# External_Sensor_Schematic.net
KiCad netlist of a schematic drawn in EAGLE
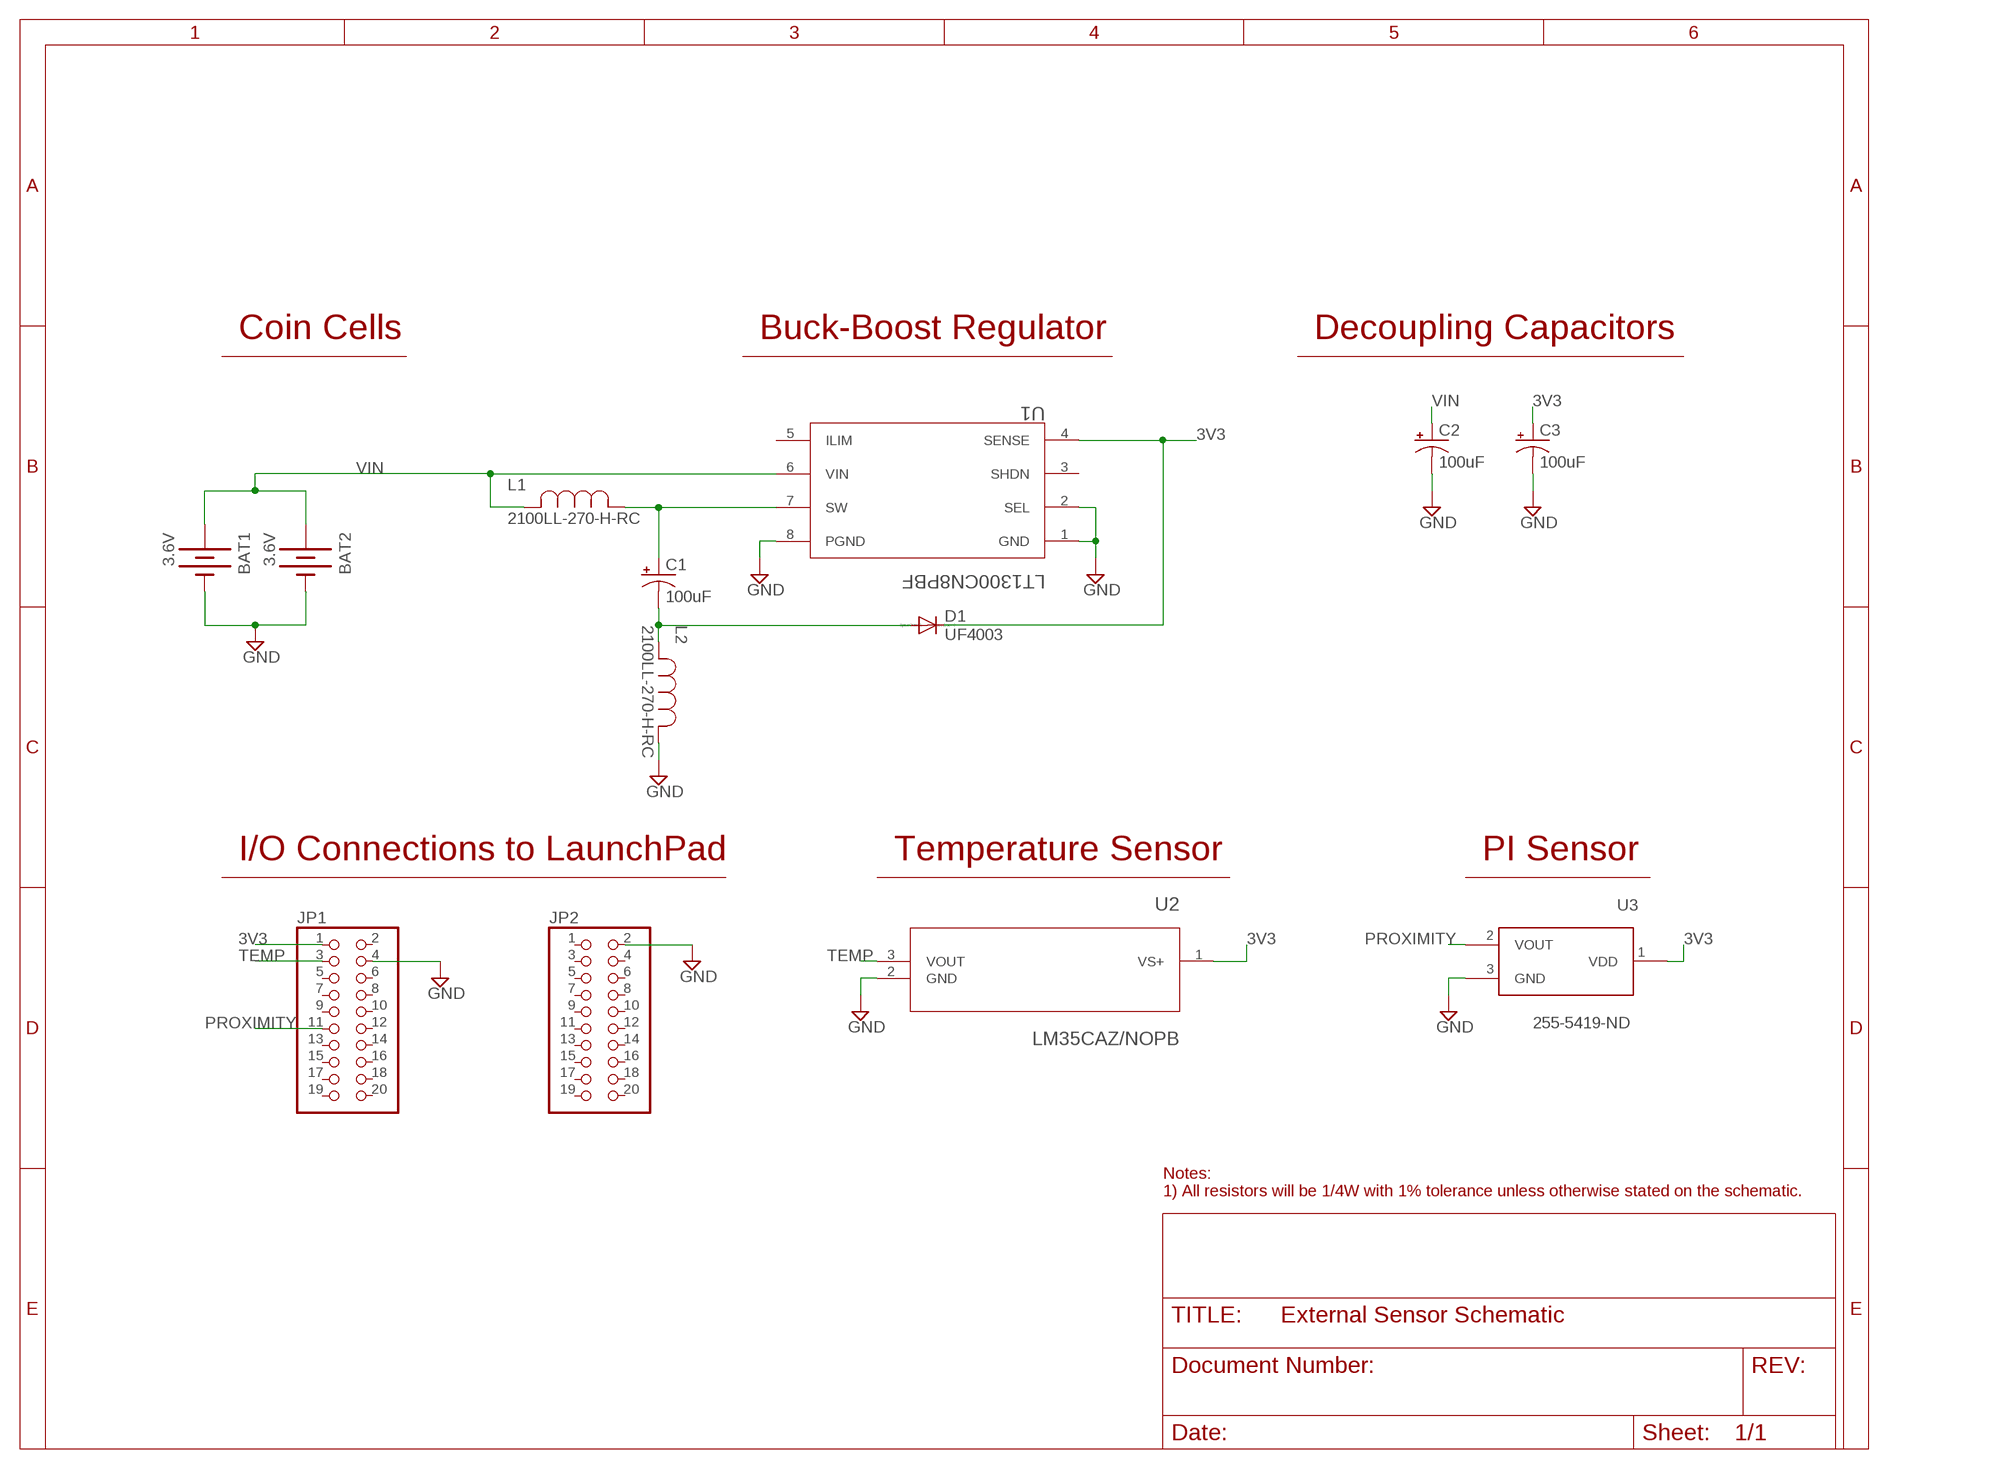
[diagram p0: schematic, sheet 1]

(export (version "E")
  (design (tool "Eeschema 10.0.6"))
  (components
    (comp (ref "BAT1")
      (value "3.6V")
      (footprint "eagle-import:BATTCON_245MM_PTH")
      (libsource (lib "eagle-import") (part "BATTERY245PTH"))
    )
    (comp (ref "BAT2")
      (value "3.6V")
      (footprint "eagle-import:BATTCON_245MM_PTH")
      (libsource (lib "eagle-import") (part "BATTERY245PTH"))
    )
    (comp (ref "C1")
      (value "100uF")
      (footprint "eagle-import:EEU-FR1H101")
      (libsource (lib "eagle-import") (part "100UF-POLAR"))
    )
    (comp (ref "C2")
      (value "100uF")
      (footprint "eagle-import:EEU-FR1H101")
      (libsource (lib "eagle-import") (part "100UF-POLAR"))
    )
    (comp (ref "C3")
      (value "100uF")
      (footprint "eagle-import:EEU-FR1H101")
      (libsource (lib "eagle-import") (part "100UF-POLAR"))
    )
    (comp (ref "D1")
      (value "UF4003")
      (footprint "eagle-import:DO41-10")
      (libsource (lib "eagle-import") (part "UF4003"))
    )
    (comp (ref "JP1")
      (value "PINHD-2X10")
      (footprint "eagle-import:2X10")
      (libsource (lib "eagle-import") (part "PINHD-2X10"))
    )
    (comp (ref "JP2")
      (value "PINHD-2X10")
      (footprint "eagle-import:2X10")
      (libsource (lib "eagle-import") (part "PINHD-2X10"))
    )
    (comp (ref "L1")
      (value "2100LL-270-H-RC")
      (footprint "eagle-import:IND_2100LL_42_H")
      (fields (field (name "MANUFACTURER_PART_NUMBER") "2100LL270HRC"))
      (libsource (lib "eagle-import") (part "2100LL-270-H-RC"))
    )
    (comp (ref "L2")
      (value "2100LL-270-H-RC")
      (footprint "eagle-import:IND_2100LL_42_H")
      (fields (field (name "MANUFACTURER_PART_NUMBER") "2100LL270HRC"))
      (libsource (lib "eagle-import") (part "2100LL-270-H-RC"))
    )
    (comp (ref "U1")
      (value "LT1300CN8PBF")
      (footprint "eagle-import:PDIP-8_N")
      (fields (field (name "MANUFACTURER_PART_NUMBER") "LT1300CN8#PBF"))
      (libsource (lib "eagle-import") (part "LT1300CN8PBF"))
    )
    (comp (ref "U2")
      (value "LM35CAZ/NOPB")
      (footprint "eagle-import:Z03A")
      (fields (field (name "MANUFACTURER_PART_NUMBER") "LM35CAZNOPB"))
      (libsource (lib "eagle-import") (part "LM35CAZ/NOPB"))
    )
    (comp (ref "U3")
      (value "PI_SENSOR_255-5419-ND")
      (footprint "eagle-import:255-5419-ND")
      (libsource (lib "eagle-import") (part "PI_SENSOR_255-5419-ND"))
    )
  )
  (nets
    (net (code "1") (name "/3V3") (class "Default")
      (node (ref "C3") (pin "P") (pinfunction "+_P") (pintype "passive"))
      (node (ref "D1") (pin "C") (pinfunction "C_C") (pintype "passive"))
      (node (ref "JP1") (pin "1") (pinfunction "1_1") (pintype "passive"))
      (node (ref "U1") (pin "4") (pinfunction "SENSE_4") (pintype "passive"))
      (node (ref "U2") (pin "1") (pinfunction "VS+_1") (pintype "input"))
      (node (ref "U3") (pin "VDD") (pinfunction "VDD_VDD") (pintype "bidirectional"))
    )
    (net (code "2") (name "/PROXIMITY") (class "Default")
      (node (ref "JP1") (pin "11") (pinfunction "11_11") (pintype "passive"))
      (node (ref "U3") (pin "VOUT") (pinfunction "VOUT_VOUT") (pintype "bidirectional"))
    )
    (net (code "3") (name "/TEMP") (class "Default")
      (node (ref "JP1") (pin "3") (pinfunction "3_3") (pintype "passive"))
      (node (ref "U2") (pin "3") (pinfunction "VOUT_3") (pintype "output"))
    )
    (net (code "4") (name "/VIN") (class "Default")
      (node (ref "BAT1") (pin "3") (pinfunction "+_3") (pintype "power_in"))
      (node (ref "BAT2") (pin "3") (pinfunction "+_3") (pintype "power_in"))
      (node (ref "C2") (pin "P") (pinfunction "+_P") (pintype "passive"))
      (node (ref "L1") (pin "2") (pinfunction "2_2") (pintype "passive"))
      (node (ref "U1") (pin "6") (pinfunction "VIN_6") (pintype "passive"))
    )
    (net (code "5") (name "GND") (class "Default")
      (node (ref "BAT1") (pin "2") (pinfunction "-_2") (pintype "power_in"))
      (node (ref "BAT2") (pin "2") (pinfunction "-_2") (pintype "power_in"))
      (node (ref "C2") (pin "G") (pinfunction "-_G") (pintype "passive"))
      (node (ref "C3") (pin "G") (pinfunction "-_G") (pintype "passive"))
      (node (ref "JP1") (pin "4") (pinfunction "4_4") (pintype "passive"))
      (node (ref "JP2") (pin "2") (pinfunction "2_2") (pintype "passive"))
      (node (ref "L2") (pin "1") (pinfunction "1_1") (pintype "passive"))
      (node (ref "U1") (pin "1") (pinfunction "GND_1") (pintype "power_in"))
      (node (ref "U1") (pin "2") (pinfunction "SEL_2") (pintype "passive"))
      (node (ref "U1") (pin "8") (pinfunction "PGND_8") (pintype "power_in"))
      (node (ref "U2") (pin "2") (pinfunction "GND_2") (pintype "passive"))
      (node (ref "U3") (pin "GND") (pinfunction "GND_GND") (pintype "bidirectional"))
    )
    (net (code "6") (name "Net-(C1-+)") (class "Default")
      (node (ref "C1") (pin "P") (pinfunction "+_P") (pintype "passive"))
      (node (ref "L1") (pin "1") (pinfunction "1_1") (pintype "passive"))
      (node (ref "U1") (pin "7") (pinfunction "SW_7") (pintype "passive"))
    )
    (net (code "7") (name "Net-(C1--)") (class "Default")
      (node (ref "C1") (pin "G") (pinfunction "-_G") (pintype "passive"))
      (node (ref "D1") (pin "A") (pinfunction "A_A") (pintype "passive"))
      (node (ref "L2") (pin "2") (pinfunction "2_2") (pintype "passive"))
    )
    (net (code "8") (name "unconnected-(JP1-Pad2)") (class "Default")
      (node (ref "JP1") (pin "2") (pinfunction "2_2") (pintype "passive"))
    )
    (net (code "9") (name "unconnected-(JP1-Pad5)") (class "Default")
      (node (ref "JP1") (pin "5") (pinfunction "5_5") (pintype "passive"))
    )
    (net (code "10") (name "unconnected-(JP1-Pad6)") (class "Default")
      (node (ref "JP1") (pin "6") (pinfunction "6_6") (pintype "passive"))
    )
    (net (code "11") (name "unconnected-(JP1-Pad7)") (class "Default")
      (node (ref "JP1") (pin "7") (pinfunction "7_7") (pintype "passive"))
    )
    (net (code "12") (name "unconnected-(JP1-Pad8)") (class "Default")
      (node (ref "JP1") (pin "8") (pinfunction "8_8") (pintype "passive"))
    )
    (net (code "13") (name "unconnected-(JP1-Pad9)") (class "Default")
      (node (ref "JP1") (pin "9") (pinfunction "9_9") (pintype "passive"))
    )
    (net (code "14") (name "unconnected-(JP1-Pad10)") (class "Default")
      (node (ref "JP1") (pin "10") (pinfunction "10_10") (pintype "passive"))
    )
    (net (code "15") (name "unconnected-(JP1-Pad12)") (class "Default")
      (node (ref "JP1") (pin "12") (pinfunction "12_12") (pintype "passive"))
    )
    (net (code "16") (name "unconnected-(JP1-Pad13)") (class "Default")
      (node (ref "JP1") (pin "13") (pinfunction "13_13") (pintype "passive"))
    )
    (net (code "17") (name "unconnected-(JP1-Pad14)") (class "Default")
      (node (ref "JP1") (pin "14") (pinfunction "14_14") (pintype "passive"))
    )
    (net (code "18") (name "unconnected-(JP1-Pad15)") (class "Default")
      (node (ref "JP1") (pin "15") (pinfunction "15_15") (pintype "passive"))
    )
    (net (code "19") (name "unconnected-(JP1-Pad16)") (class "Default")
      (node (ref "JP1") (pin "16") (pinfunction "16_16") (pintype "passive"))
    )
    (net (code "20") (name "unconnected-(JP1-Pad17)") (class "Default")
      (node (ref "JP1") (pin "17") (pinfunction "17_17") (pintype "passive"))
    )
    (net (code "21") (name "unconnected-(JP1-Pad18)") (class "Default")
      (node (ref "JP1") (pin "18") (pinfunction "18_18") (pintype "passive"))
    )
    (net (code "22") (name "unconnected-(JP1-Pad19)") (class "Default")
      (node (ref "JP1") (pin "19") (pinfunction "19_19") (pintype "passive"))
    )
    (net (code "23") (name "unconnected-(JP1-Pad20)") (class "Default")
      (node (ref "JP1") (pin "20") (pinfunction "20_20") (pintype "passive"))
    )
    (net (code "24") (name "unconnected-(JP2-Pad1)") (class "Default")
      (node (ref "JP2") (pin "1") (pinfunction "1_1") (pintype "passive"))
    )
    (net (code "25") (name "unconnected-(JP2-Pad3)") (class "Default")
      (node (ref "JP2") (pin "3") (pinfunction "3_3") (pintype "passive"))
    )
    (net (code "26") (name "unconnected-(JP2-Pad4)") (class "Default")
      (node (ref "JP2") (pin "4") (pinfunction "4_4") (pintype "passive"))
    )
    (net (code "27") (name "unconnected-(JP2-Pad5)") (class "Default")
      (node (ref "JP2") (pin "5") (pinfunction "5_5") (pintype "passive"))
    )
    (net (code "28") (name "unconnected-(JP2-Pad6)") (class "Default")
      (node (ref "JP2") (pin "6") (pinfunction "6_6") (pintype "passive"))
    )
    (net (code "29") (name "unconnected-(JP2-Pad7)") (class "Default")
      (node (ref "JP2") (pin "7") (pinfunction "7_7") (pintype "passive"))
    )
    (net (code "30") (name "unconnected-(JP2-Pad8)") (class "Default")
      (node (ref "JP2") (pin "8") (pinfunction "8_8") (pintype "passive"))
    )
    (net (code "31") (name "unconnected-(JP2-Pad9)") (class "Default")
      (node (ref "JP2") (pin "9") (pinfunction "9_9") (pintype "passive"))
    )
    (net (code "32") (name "unconnected-(JP2-Pad10)") (class "Default")
      (node (ref "JP2") (pin "10") (pinfunction "10_10") (pintype "passive"))
    )
    (net (code "33") (name "unconnected-(JP2-Pad11)") (class "Default")
      (node (ref "JP2") (pin "11") (pinfunction "11_11") (pintype "passive"))
    )
    (net (code "34") (name "unconnected-(JP2-Pad12)") (class "Default")
      (node (ref "JP2") (pin "12") (pinfunction "12_12") (pintype "passive"))
    )
    (net (code "35") (name "unconnected-(JP2-Pad13)") (class "Default")
      (node (ref "JP2") (pin "13") (pinfunction "13_13") (pintype "passive"))
    )
    (net (code "36") (name "unconnected-(JP2-Pad14)") (class "Default")
      (node (ref "JP2") (pin "14") (pinfunction "14_14") (pintype "passive"))
    )
    (net (code "37") (name "unconnected-(JP2-Pad15)") (class "Default")
      (node (ref "JP2") (pin "15") (pinfunction "15_15") (pintype "passive"))
    )
    (net (code "38") (name "unconnected-(JP2-Pad16)") (class "Default")
      (node (ref "JP2") (pin "16") (pinfunction "16_16") (pintype "passive"))
    )
    (net (code "39") (name "unconnected-(JP2-Pad17)") (class "Default")
      (node (ref "JP2") (pin "17") (pinfunction "17_17") (pintype "passive"))
    )
    (net (code "40") (name "unconnected-(JP2-Pad18)") (class "Default")
      (node (ref "JP2") (pin "18") (pinfunction "18_18") (pintype "passive"))
    )
    (net (code "41") (name "unconnected-(JP2-Pad19)") (class "Default")
      (node (ref "JP2") (pin "19") (pinfunction "19_19") (pintype "passive"))
    )
    (net (code "42") (name "unconnected-(JP2-Pad20)") (class "Default")
      (node (ref "JP2") (pin "20") (pinfunction "20_20") (pintype "passive"))
    )
    (net (code "43") (name "unconnected-(U1-ILIM-Pad5)") (class "Default")
      (node (ref "U1") (pin "5") (pinfunction "ILIM_5") (pintype "passive"))
    )
    (net (code "44") (name "unconnected-(U1-SHDN-Pad3)") (class "Default")
      (node (ref "U1") (pin "3") (pinfunction "SHDN_3") (pintype "passive"))
    )
  )
)
